# SD_Card.net
KiCad netlist of a schematic drawn in Altium Designer
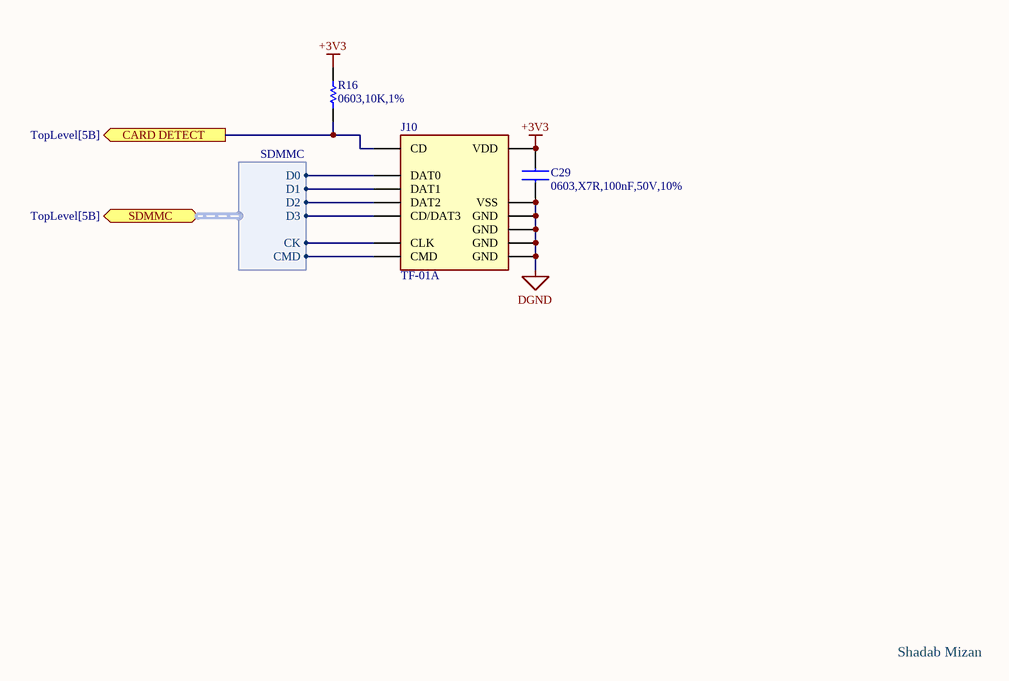
[diagram p0: SD Card.SchDoc]

(export (version "E")
  (design (tool "Eeschema 10.0.6"))
  (components
    (comp (ref "C29")
      (value "0603,X7R,100nF,50V,10%")
      (footprint "CAPC1608X90N")
      (description "50V 100nF X7R ±10% 0603 Multilayer Ceramic Capacitors MLCC - SMD/SMT ROHS")
      (fields (field (name "LCSC PART #") "C14663") (field (name "MANU PART #") "CC0603KRX7R9BB104"))
      (libsource (lib "flight-controller") (part "CC0603KRX7R9BB104"))
    )
    (comp (ref "J10")
      (value "TF-01A")
      (footprint "TF-SMD_TF-01A")
      (description "Micro SD card (TF card) Connector and Ejector Push-Push Surface Mount")
      (fields (field (name "LCSC PART #") "C41426929"))
      (libsource (lib "flight-controller") (part "TF-01A"))
    )
    (comp (ref "R16")
      (value "0603,10K,1%")
      (footprint "RESC1608X90N")
      (description "100mW Thick Film Resistor 75V ±100ppm/℃ ±1% 10kΩ 0603 Chip Resistor - Surface Mount ROHS")
      (fields (field (name "LCSC PART #") "C25804") (field (name "MANU PART #") "0603WAF1002T5E"))
      (libsource (lib "flight-controller") (part "0603WAF1002T5E"))
    )
  )
  (nets
    (net (code "2") (name "+3V3") (class "Default")
      (node (ref "C29") (pin "2") (pinfunction "2_2") (pintype "passive"))
      (node (ref "J10") (pin "4") (pinfunction "VDD_4") (pintype "passive"))
      (node (ref "R16") (pin "2") (pinfunction "2_2") (pintype "passive"))
    )
    (net (code "3") (name "/CARD DETECT") (class "Default")
      (node (ref "J10") (pin "9") (pinfunction "CD_9") (pintype "passive"))
      (node (ref "R16") (pin "1") (pinfunction "1_1") (pintype "passive"))
    )
    (net (code "4") (name "/CK") (class "Default")
      (node (ref "J10") (pin "5") (pinfunction "CLK_5") (pintype "passive"))
    )
    (net (code "5") (name "/CMD") (class "Default")
      (node (ref "J10") (pin "3") (pinfunction "CMD_3") (pintype "passive"))
    )
    (net (code "6") (name "/D0") (class "Default")
      (node (ref "J10") (pin "7") (pinfunction "DAT0_7") (pintype "passive"))
    )
    (net (code "7") (name "/D1") (class "Default")
      (node (ref "J10") (pin "8") (pinfunction "DAT1_8") (pintype "passive"))
    )
    (net (code "8") (name "/D2") (class "Default")
      (node (ref "J10") (pin "1") (pinfunction "DAT2_1") (pintype "passive"))
    )
    (net (code "9") (name "/D3") (class "Default")
      (node (ref "J10") (pin "2") (pinfunction "CD/DAT3_2") (pintype "passive"))
    )
    (net (code "11") (name "DGND") (class "Default")
      (node (ref "C29") (pin "1") (pinfunction "1_1") (pintype "passive"))
      (node (ref "J10") (pin "10") (pinfunction "GND_10") (pintype "passive"))
      (node (ref "J10") (pin "11") (pinfunction "GND_11") (pintype "passive"))
      (node (ref "J10") (pin "12") (pinfunction "GND_12") (pintype "passive"))
      (node (ref "J10") (pin "13") (pinfunction "GND_13") (pintype "passive"))
      (node (ref "J10") (pin "6") (pinfunction "VSS_6") (pintype "passive"))
    )
  )
)
